# IotaWatt4_1.net
KiCad netlist of a schematic drawn in EAGLE
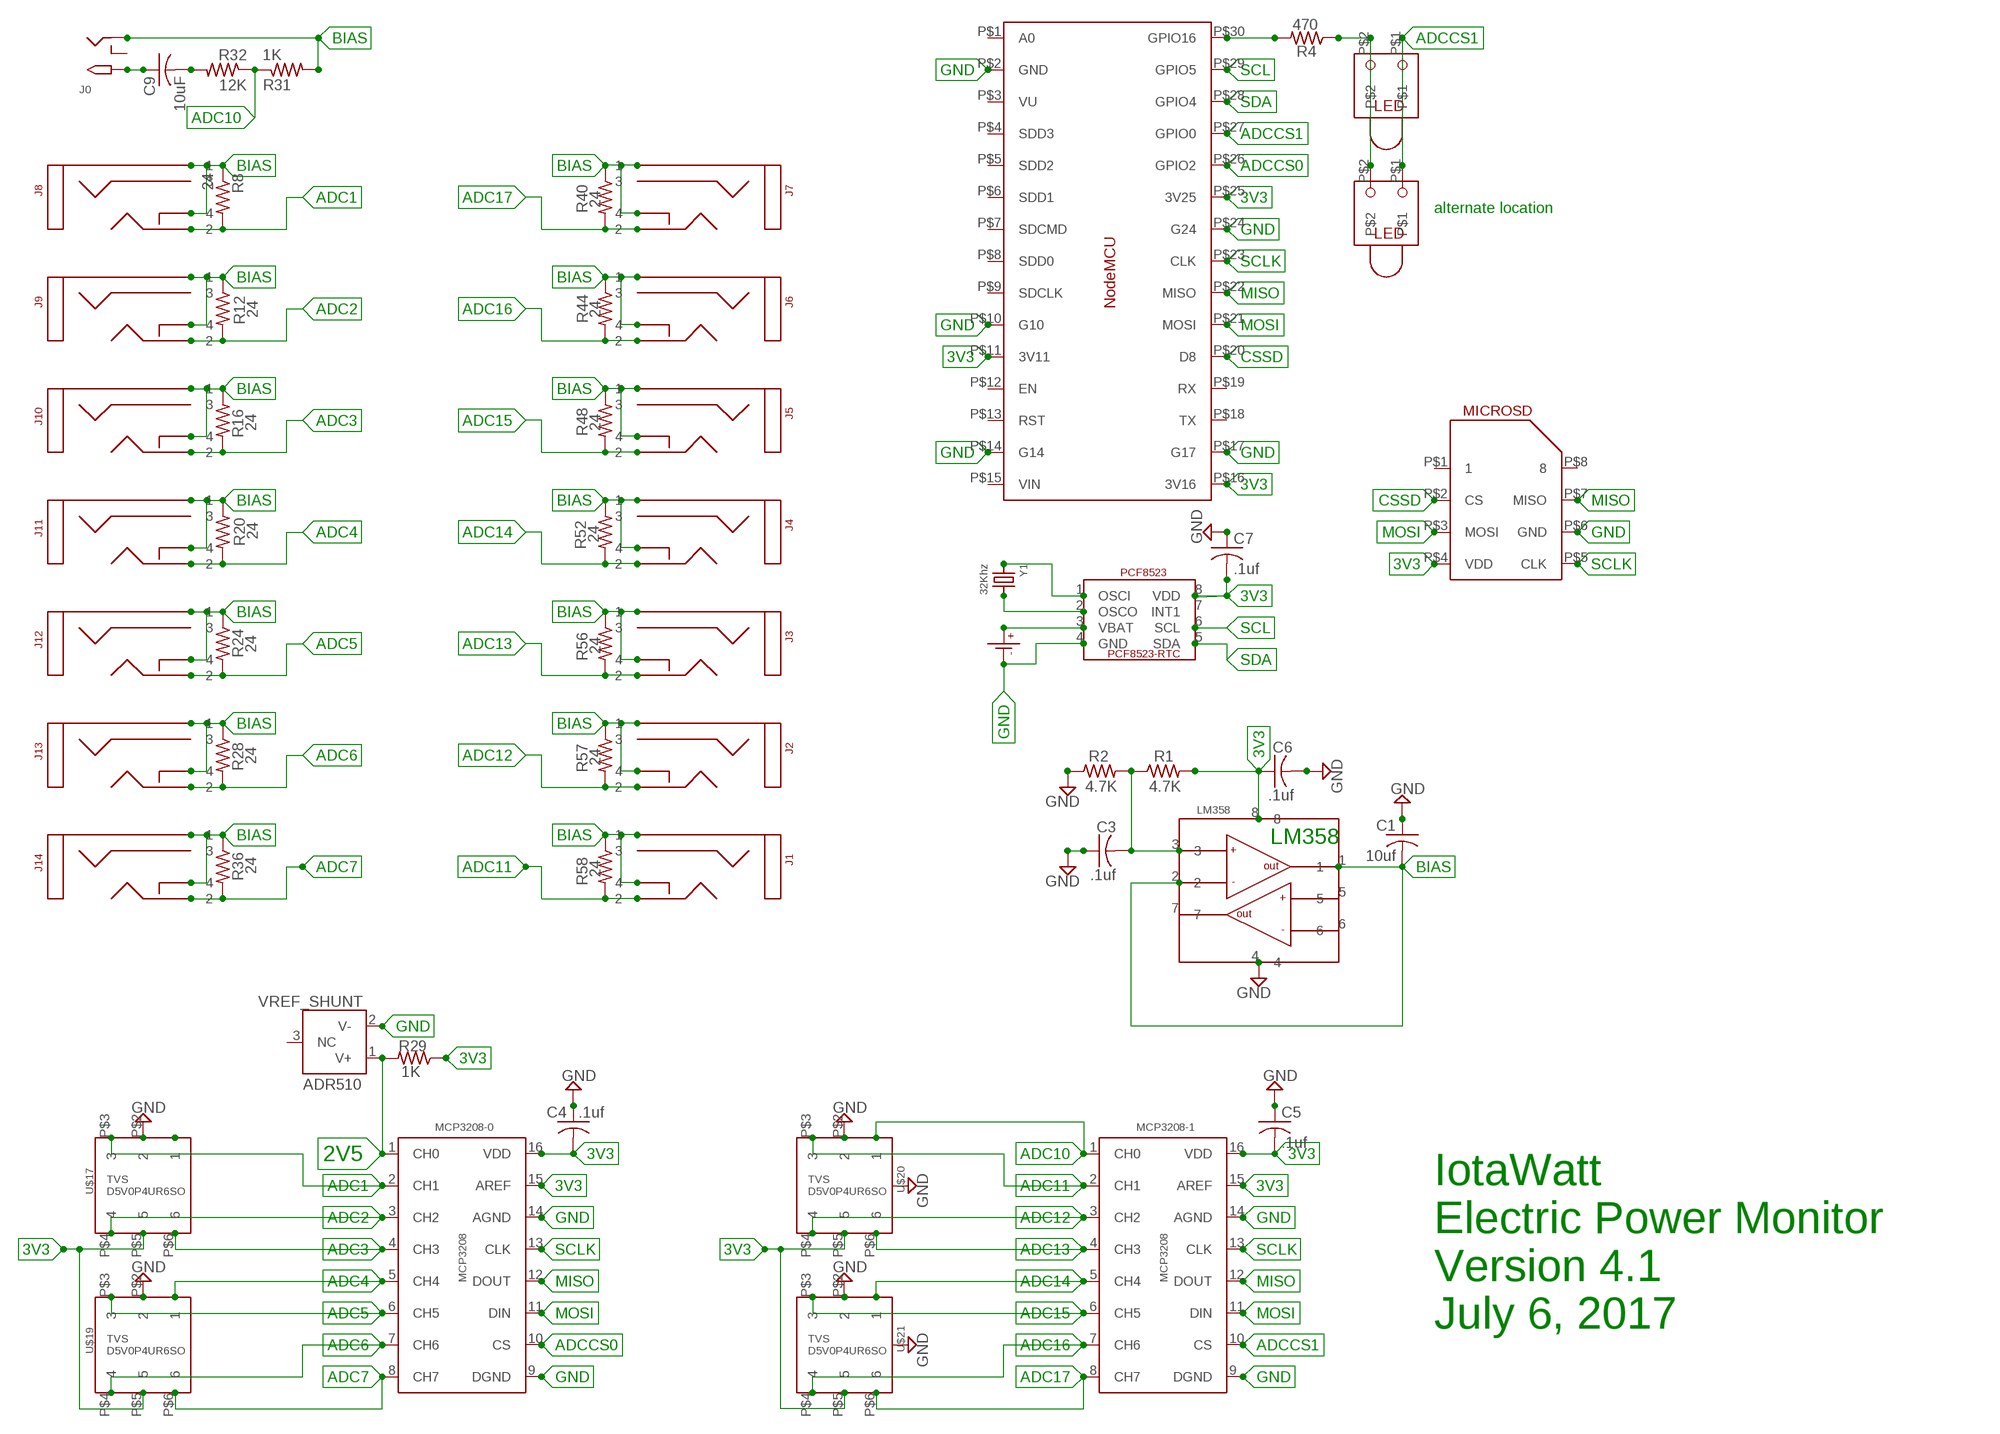
[diagram p0: schematic, sheet 1]

(export (version "E")
  (design (tool "Eeschema 10.0.6"))
  (components
    (comp (ref "ADR510")
      (value "VREF_SHUNT")
      (footprint "eagle-import:SOT23_3")
      (libsource (lib "eagle-import") (part "VREF_SHUNT"))
    )
    (comp (ref "C1")
      (value "10uf")
      (footprint "eagle-import:C0805")
      (libsource (lib "eagle-import") (part "C-USC0805"))
    )
    (comp (ref "C3")
      (value ".1uf")
      (footprint "eagle-import:C0805")
      (libsource (lib "eagle-import") (part "C-USC0805"))
    )
    (comp (ref "C4")
      (value ".1uf")
      (footprint "eagle-import:C0402")
      (libsource (lib "eagle-import") (part "C-USC0402"))
    )
    (comp (ref "C5")
      (value ".1uf")
      (footprint "eagle-import:C0402")
      (libsource (lib "eagle-import") (part "C-USC0402"))
    )
    (comp (ref "C6")
      (value ".1uf")
      (footprint "eagle-import:C0402")
      (libsource (lib "eagle-import") (part "C-USC0402"))
    )
    (comp (ref "C7")
      (value ".1uf")
      (footprint "eagle-import:C0402")
      (libsource (lib "eagle-import") (part "C-USC0402"))
    )
    (comp (ref "C9")
      (value "10uF")
      (footprint "eagle-import:C0805")
      (libsource (lib "eagle-import") (part "C-USC0805"))
    )
    (comp (ref "J0")
      (value "2.1MMJACKSMT")
      (footprint "eagle-import:DCJACK_2MM_SMT")
      (libsource (lib "eagle-import") (part "2.1MMJACKSMT"))
    )
    (comp (ref "J1")
      (value "STEREO_SMD")
      (footprint "eagle-import:STEREO_SMT")
      (libsource (lib "eagle-import") (part "STEREO_SMD"))
    )
    (comp (ref "J2")
      (value "STEREO_SMD")
      (footprint "eagle-import:STEREO_SMT")
      (libsource (lib "eagle-import") (part "STEREO_SMD"))
    )
    (comp (ref "J3")
      (value "STEREO_SMD")
      (footprint "eagle-import:STEREO_SMT")
      (libsource (lib "eagle-import") (part "STEREO_SMD"))
    )
    (comp (ref "J4")
      (value "STEREO_SMD")
      (footprint "eagle-import:STEREO_SMT")
      (libsource (lib "eagle-import") (part "STEREO_SMD"))
    )
    (comp (ref "J5")
      (value "STEREO_SMD")
      (footprint "eagle-import:STEREO_SMT")
      (libsource (lib "eagle-import") (part "STEREO_SMD"))
    )
    (comp (ref "J6")
      (value "STEREO_SMD")
      (footprint "eagle-import:STEREO_SMT")
      (libsource (lib "eagle-import") (part "STEREO_SMD"))
    )
    (comp (ref "J7")
      (value "STEREO_SMD")
      (footprint "eagle-import:STEREO_SMT")
      (libsource (lib "eagle-import") (part "STEREO_SMD"))
    )
    (comp (ref "J8")
      (value "STEREO_SMD")
      (footprint "eagle-import:STEREO_SMT")
      (libsource (lib "eagle-import") (part "STEREO_SMD"))
    )
    (comp (ref "J9")
      (value "STEREO_SMD")
      (footprint "eagle-import:STEREO_SMT")
      (libsource (lib "eagle-import") (part "STEREO_SMD"))
    )
    (comp (ref "J10")
      (value "STEREO_SMD")
      (footprint "eagle-import:STEREO_SMT")
      (libsource (lib "eagle-import") (part "STEREO_SMD"))
    )
    (comp (ref "J11")
      (value "STEREO_SMD")
      (footprint "eagle-import:STEREO_SMT")
      (libsource (lib "eagle-import") (part "STEREO_SMD"))
    )
    (comp (ref "J12")
      (value "STEREO_SMD")
      (footprint "eagle-import:STEREO_SMT")
      (libsource (lib "eagle-import") (part "STEREO_SMD"))
    )
    (comp (ref "J13")
      (value "STEREO_SMD")
      (footprint "eagle-import:STEREO_SMT")
      (libsource (lib "eagle-import") (part "STEREO_SMD"))
    )
    (comp (ref "J14")
      (value "STEREO_SMD")
      (footprint "eagle-import:STEREO_SMT")
      (libsource (lib "eagle-import") (part "STEREO_SMD"))
    )
    (comp (ref "MCP3208-0")
      (value "MCP3208")
      (footprint "eagle-import:SOIC_16")
      (libsource (lib "eagle-import") (part "MCP3208"))
    )
    (comp (ref "MCP3208-1")
      (value "MCP3208")
      (footprint "eagle-import:SOIC_16")
      (libsource (lib "eagle-import") (part "MCP3208"))
    )
    (comp (ref "MICROSD")
      (value "MICROSD_PUSH/PULL")
      (footprint "eagle-import:MICROSD")
      (libsource (lib "eagle-import") (part "MICROSD_PUSH/PULL"))
    )
    (comp (ref "PCF8523")
      (value "PCF8523_RTC")
      (footprint "eagle-import:SOIC_8")
      (libsource (lib "eagle-import") (part "PCF8523_RTC"))
    )
    (comp (ref "R1")
      (value "4.7K")
      (footprint "eagle-import:R0805")
      (libsource (lib "eagle-import") (part "R-US_R0805"))
    )
    (comp (ref "R2")
      (value "4.7K")
      (footprint "eagle-import:R0805")
      (libsource (lib "eagle-import") (part "R-US_R0805"))
    )
    (comp (ref "R4")
      (value "470")
      (footprint "eagle-import:R0805")
      (libsource (lib "eagle-import") (part "R-US_R0805"))
    )
    (comp (ref "R8")
      (value "24")
      (footprint "eagle-import:R0805")
      (libsource (lib "eagle-import") (part "R-US_R0805"))
    )
    (comp (ref "R12")
      (value "24")
      (footprint "eagle-import:R0805")
      (libsource (lib "eagle-import") (part "R-US_R0805"))
    )
    (comp (ref "R16")
      (value "24")
      (footprint "eagle-import:R0805")
      (libsource (lib "eagle-import") (part "R-US_R0805"))
    )
    (comp (ref "R20")
      (value "24")
      (footprint "eagle-import:R0805")
      (libsource (lib "eagle-import") (part "R-US_R0805"))
    )
    (comp (ref "R24")
      (value "24")
      (footprint "eagle-import:R0805")
      (libsource (lib "eagle-import") (part "R-US_R0805"))
    )
    (comp (ref "R28")
      (value "24")
      (footprint "eagle-import:R0805")
      (libsource (lib "eagle-import") (part "R-US_R0805"))
    )
    (comp (ref "R29")
      (value "1K")
      (footprint "eagle-import:R0805")
      (libsource (lib "eagle-import") (part "R-US_R0805"))
    )
    (comp (ref "R31")
      (value "1K")
      (footprint "eagle-import:R0805")
      (libsource (lib "eagle-import") (part "R-US_R0805"))
    )
    (comp (ref "R32")
      (value "12K")
      (footprint "eagle-import:R0805")
      (libsource (lib "eagle-import") (part "R-US_R0805"))
    )
    (comp (ref "R36")
      (value "24")
      (footprint "eagle-import:R0805")
      (libsource (lib "eagle-import") (part "R-US_R0805"))
    )
    (comp (ref "R40")
      (value "24")
      (footprint "eagle-import:R0805")
      (libsource (lib "eagle-import") (part "R-US_R0805"))
    )
    (comp (ref "R44")
      (value "24")
      (footprint "eagle-import:R0805")
      (libsource (lib "eagle-import") (part "R-US_R0805"))
    )
    (comp (ref "R48")
      (value "24")
      (footprint "eagle-import:R0805")
      (libsource (lib "eagle-import") (part "R-US_R0805"))
    )
    (comp (ref "R52")
      (value "24")
      (footprint "eagle-import:R0805")
      (libsource (lib "eagle-import") (part "R-US_R0805"))
    )
    (comp (ref "R56")
      (value "24")
      (footprint "eagle-import:R0805")
      (libsource (lib "eagle-import") (part "R-US_R0805"))
    )
    (comp (ref "R57")
      (value "24")
      (footprint "eagle-import:R0805")
      (libsource (lib "eagle-import") (part "R-US_R0805"))
    )
    (comp (ref "R58")
      (value "24")
      (footprint "eagle-import:R0805")
      (libsource (lib "eagle-import") (part "R-US_R0805"))
    )
    (comp (ref "U$15")
      (value "LED_RT_TRH")
      (footprint "eagle-import:LED_TH_RT")
      (libsource (lib "eagle-import") (part "LED_RT_TRH"))
    )
    (comp (ref "U$16")
      (value "NODEMCU")
      (footprint "eagle-import:NODEMCU")
      (libsource (lib "eagle-import") (part "NODEMCU"))
    )
    (comp (ref "U$17")
      (value "TVS_4CHAN_ARRAY")
      (footprint "eagle-import:SC-74")
      (libsource (lib "eagle-import") (part "TVS_4CHAN_ARRAY"))
    )
    (comp (ref "U$18")
      (value "CR1220SMD")
      (footprint "eagle-import:CR1220SMD")
      (libsource (lib "eagle-import") (part "CR1220SMD"))
    )
    (comp (ref "U$19")
      (value "TVS_4CHAN_ARRAY")
      (footprint "eagle-import:SC-74")
      (libsource (lib "eagle-import") (part "TVS_4CHAN_ARRAY"))
    )
    (comp (ref "U$20")
      (value "TVS_4CHAN_ARRAY")
      (footprint "eagle-import:SC-74")
      (libsource (lib "eagle-import") (part "TVS_4CHAN_ARRAY"))
    )
    (comp (ref "U$21")
      (value "TVS_4CHAN_ARRAY")
      (footprint "eagle-import:SC-74")
      (libsource (lib "eagle-import") (part "TVS_4CHAN_ARRAY"))
    )
    (comp (ref "U$22")
      (value "LM358_DUAL_OP-AMP")
      (footprint "eagle-import:SOIC_8")
      (libsource (lib "eagle-import") (part "LM358_DUAL_OP-AMP"))
    )
    (comp (ref "U$23")
      (value "LED_RT_TRH")
      (footprint "eagle-import:LED_TH_RT")
      (libsource (lib "eagle-import") (part "LED_RT_TRH"))
    )
    (comp (ref "Y1")
      (value "32Khz")
      (footprint "eagle-import:CRYSTAL_8X3.8")
      (libsource (lib "eagle-import") (part "CRYSTAL8X3.8SMT"))
    )
  )
  (nets
    (net (code "1") (name "2V5") (class "Default")
      (node (ref "ADR510") (pin "1") (pinfunction "V+_1") (pintype "bidirectional"))
      (node (ref "MCP3208-0") (pin "1") (pinfunction "CH0_1") (pintype "input"))
      (node (ref "R29") (pin "2") (pinfunction "2_2") (pintype "passive"))
    )
    (net (code "2") (name "3V3") (class "Default")
      (node (ref "C4") (pin "2") (pinfunction "2_2") (pintype "passive"))
      (node (ref "C5") (pin "2") (pinfunction "2_2") (pintype "passive"))
      (node (ref "C6") (pin "1") (pinfunction "1_1") (pintype "passive"))
      (node (ref "C7") (pin "2") (pinfunction "2_2") (pintype "passive"))
      (node (ref "MCP3208-0") (pin "15") (pinfunction "AREF_15") (pintype "input"))
      (node (ref "MCP3208-0") (pin "16") (pinfunction "VDD_16") (pintype "bidirectional"))
      (node (ref "MCP3208-1") (pin "15") (pinfunction "AREF_15") (pintype "input"))
      (node (ref "MCP3208-1") (pin "16") (pinfunction "VDD_16") (pintype "bidirectional"))
      (node (ref "MICROSD") (pin "P$4") (pinfunction "VDD_P$4") (pintype "bidirectional"))
      (node (ref "PCF8523") (pin "8") (pinfunction "VDD_8") (pintype "bidirectional"))
      (node (ref "R1") (pin "2") (pinfunction "2_2") (pintype "passive"))
      (node (ref "R29") (pin "1") (pinfunction "1_1") (pintype "passive"))
      (node (ref "U$16") (pin "P$11") (pinfunction "3V11_P$11") (pintype "bidirectional"))
      (node (ref "U$16") (pin "P$16") (pinfunction "3V16_P$16") (pintype "bidirectional"))
      (node (ref "U$16") (pin "P$25") (pinfunction "3V25_P$25") (pintype "bidirectional"))
      (node (ref "U$17") (pin "P$5") (pinfunction "5_P$5") (pintype "bidirectional"))
      (node (ref "U$19") (pin "P$5") (pinfunction "5_P$5") (pintype "bidirectional"))
      (node (ref "U$20") (pin "P$5") (pinfunction "5_P$5") (pintype "bidirectional"))
      (node (ref "U$21") (pin "P$5") (pinfunction "5_P$5") (pintype "bidirectional"))
      (node (ref "U$22") (pin "8") (pinfunction "8_8") (pintype "bidirectional"))
    )
    (net (code "3") (name "ADC1") (class "Default")
      (node (ref "J8") (pin "P$2") (pinfunction "2_P$2") (pintype "bidirectional"))
      (node (ref "MCP3208-0") (pin "2") (pinfunction "CH1_2") (pintype "input"))
      (node (ref "R8") (pin "2") (pinfunction "2_2") (pintype "passive"))
      (node (ref "U$17") (pin "P$3") (pinfunction "3_P$3") (pintype "bidirectional"))
    )
    (net (code "4") (name "ADC2") (class "Default")
      (node (ref "J9") (pin "P$2") (pinfunction "2_P$2") (pintype "bidirectional"))
      (node (ref "MCP3208-0") (pin "3") (pinfunction "CH2_3") (pintype "input"))
      (node (ref "R12") (pin "2") (pinfunction "2_2") (pintype "passive"))
      (node (ref "U$17") (pin "P$4") (pinfunction "4_P$4") (pintype "bidirectional"))
    )
    (net (code "5") (name "ADC3") (class "Default")
      (node (ref "J10") (pin "P$2") (pinfunction "2_P$2") (pintype "bidirectional"))
      (node (ref "MCP3208-0") (pin "4") (pinfunction "CH3_4") (pintype "input"))
      (node (ref "R16") (pin "2") (pinfunction "2_2") (pintype "passive"))
      (node (ref "U$17") (pin "P$6") (pinfunction "6_P$6") (pintype "bidirectional"))
    )
    (net (code "6") (name "ADC4") (class "Default")
      (node (ref "J11") (pin "P$2") (pinfunction "2_P$2") (pintype "bidirectional"))
      (node (ref "MCP3208-0") (pin "5") (pinfunction "CH4_5") (pintype "bidirectional"))
      (node (ref "R20") (pin "2") (pinfunction "2_2") (pintype "passive"))
      (node (ref "U$19") (pin "P$1") (pinfunction "1_P$1") (pintype "bidirectional"))
    )
    (net (code "7") (name "ADC5") (class "Default")
      (node (ref "J12") (pin "P$2") (pinfunction "2_P$2") (pintype "bidirectional"))
      (node (ref "MCP3208-0") (pin "6") (pinfunction "CH5_6") (pintype "bidirectional"))
      (node (ref "R24") (pin "2") (pinfunction "2_2") (pintype "passive"))
      (node (ref "U$19") (pin "P$3") (pinfunction "3_P$3") (pintype "bidirectional"))
    )
    (net (code "8") (name "ADC6") (class "Default")
      (node (ref "J13") (pin "P$2") (pinfunction "2_P$2") (pintype "bidirectional"))
      (node (ref "MCP3208-0") (pin "7") (pinfunction "CH6_7") (pintype "input"))
      (node (ref "R28") (pin "2") (pinfunction "2_2") (pintype "passive"))
      (node (ref "U$19") (pin "P$4") (pinfunction "4_P$4") (pintype "bidirectional"))
    )
    (net (code "9") (name "ADC7") (class "Default")
      (node (ref "J14") (pin "P$2") (pinfunction "2_P$2") (pintype "bidirectional"))
      (node (ref "MCP3208-0") (pin "8") (pinfunction "CH7_8") (pintype "bidirectional"))
      (node (ref "R36") (pin "2") (pinfunction "2_2") (pintype "passive"))
      (node (ref "U$19") (pin "P$6") (pinfunction "6_P$6") (pintype "bidirectional"))
    )
    (net (code "10") (name "ADC10") (class "Default")
      (node (ref "MCP3208-1") (pin "1") (pinfunction "CH0_1") (pintype "input"))
      (node (ref "R31") (pin "1") (pinfunction "1_1") (pintype "passive"))
      (node (ref "R32") (pin "1") (pinfunction "1_1") (pintype "passive"))
      (node (ref "U$20") (pin "P$1") (pinfunction "1_P$1") (pintype "bidirectional"))
    )
    (net (code "11") (name "ADC11") (class "Default")
      (node (ref "J1") (pin "P$2") (pinfunction "2_P$2") (pintype "bidirectional"))
      (node (ref "MCP3208-1") (pin "2") (pinfunction "CH1_2") (pintype "input"))
      (node (ref "R58") (pin "2") (pinfunction "2_2") (pintype "passive"))
      (node (ref "U$20") (pin "P$3") (pinfunction "3_P$3") (pintype "bidirectional"))
    )
    (net (code "12") (name "ADC12") (class "Default")
      (node (ref "J2") (pin "P$2") (pinfunction "2_P$2") (pintype "bidirectional"))
      (node (ref "MCP3208-1") (pin "3") (pinfunction "CH2_3") (pintype "input"))
      (node (ref "R57") (pin "2") (pinfunction "2_2") (pintype "passive"))
      (node (ref "U$20") (pin "P$4") (pinfunction "4_P$4") (pintype "bidirectional"))
    )
    (net (code "13") (name "ADC13") (class "Default")
      (node (ref "J3") (pin "P$2") (pinfunction "2_P$2") (pintype "bidirectional"))
      (node (ref "MCP3208-1") (pin "4") (pinfunction "CH3_4") (pintype "input"))
      (node (ref "R56") (pin "2") (pinfunction "2_2") (pintype "passive"))
      (node (ref "U$20") (pin "P$6") (pinfunction "6_P$6") (pintype "bidirectional"))
    )
    (net (code "14") (name "ADC14") (class "Default")
      (node (ref "J4") (pin "P$2") (pinfunction "2_P$2") (pintype "bidirectional"))
      (node (ref "MCP3208-1") (pin "5") (pinfunction "CH4_5") (pintype "bidirectional"))
      (node (ref "R52") (pin "2") (pinfunction "2_2") (pintype "passive"))
      (node (ref "U$21") (pin "P$1") (pinfunction "1_P$1") (pintype "bidirectional"))
    )
    (net (code "15") (name "ADC15") (class "Default")
      (node (ref "J5") (pin "P$2") (pinfunction "2_P$2") (pintype "bidirectional"))
      (node (ref "MCP3208-1") (pin "6") (pinfunction "CH5_6") (pintype "bidirectional"))
      (node (ref "R48") (pin "2") (pinfunction "2_2") (pintype "passive"))
      (node (ref "U$21") (pin "P$3") (pinfunction "3_P$3") (pintype "bidirectional"))
    )
    (net (code "16") (name "ADC16") (class "Default")
      (node (ref "J6") (pin "P$2") (pinfunction "2_P$2") (pintype "bidirectional"))
      (node (ref "MCP3208-1") (pin "7") (pinfunction "CH6_7") (pintype "input"))
      (node (ref "R44") (pin "2") (pinfunction "2_2") (pintype "passive"))
      (node (ref "U$21") (pin "P$4") (pinfunction "4_P$4") (pintype "bidirectional"))
    )
    (net (code "17") (name "ADC17") (class "Default")
      (node (ref "J7") (pin "P$2") (pinfunction "2_P$2") (pintype "bidirectional"))
      (node (ref "MCP3208-1") (pin "8") (pinfunction "CH7_8") (pintype "bidirectional"))
      (node (ref "R40") (pin "2") (pinfunction "2_2") (pintype "passive"))
      (node (ref "U$21") (pin "P$6") (pinfunction "6_P$6") (pintype "bidirectional"))
    )
    (net (code "18") (name "ADCCS0") (class "Default")
      (node (ref "MCP3208-0") (pin "10") (pinfunction "CS_10") (pintype "input"))
      (node (ref "U$16") (pin "P$26") (pinfunction "GPIO2_P$26") (pintype "bidirectional"))
    )
    (net (code "19") (name "ADCCS1") (class "Default")
      (node (ref "MCP3208-1") (pin "10") (pinfunction "CS_10") (pintype "input"))
      (node (ref "U$15") (pin "P$1") (pinfunction "P$1_P$1") (pintype "bidirectional"))
      (node (ref "U$16") (pin "P$27") (pinfunction "GPIO0_P$27") (pintype "bidirectional"))
      (node (ref "U$23") (pin "P$1") (pinfunction "P$1_P$1") (pintype "bidirectional"))
    )
    (net (code "20") (name "BIAS") (class "Default")
      (node (ref "C1") (pin "2") (pinfunction "2_2") (pintype "passive"))
      (node (ref "J0") (pin "GND") (pinfunction "RING_GND") (pintype "bidirectional"))
      (node (ref "J1") (pin "P$1") (pinfunction "1_P$1") (pintype "bidirectional"))
      (node (ref "J1") (pin "P$4") (pinfunction "4_P$4") (pintype "bidirectional"))
      (node (ref "J10") (pin "P$1") (pinfunction "1_P$1") (pintype "bidirectional"))
      (node (ref "J10") (pin "P$4") (pinfunction "4_P$4") (pintype "bidirectional"))
      (node (ref "J11") (pin "P$1") (pinfunction "1_P$1") (pintype "bidirectional"))
      (node (ref "J11") (pin "P$4") (pinfunction "4_P$4") (pintype "bidirectional"))
      (node (ref "J12") (pin "P$1") (pinfunction "1_P$1") (pintype "bidirectional"))
      (node (ref "J12") (pin "P$4") (pinfunction "4_P$4") (pintype "bidirectional"))
      (node (ref "J13") (pin "P$1") (pinfunction "1_P$1") (pintype "bidirectional"))
      (node (ref "J13") (pin "P$4") (pinfunction "4_P$4") (pintype "bidirectional"))
      (node (ref "J14") (pin "P$1") (pinfunction "1_P$1") (pintype "bidirectional"))
      (node (ref "J14") (pin "P$4") (pinfunction "4_P$4") (pintype "bidirectional"))
      (node (ref "J2") (pin "P$1") (pinfunction "1_P$1") (pintype "bidirectional"))
      (node (ref "J2") (pin "P$4") (pinfunction "4_P$4") (pintype "bidirectional"))
      (node (ref "J3") (pin "P$1") (pinfunction "1_P$1") (pintype "bidirectional"))
      (node (ref "J3") (pin "P$4") (pinfunction "4_P$4") (pintype "bidirectional"))
      (node (ref "J4") (pin "P$1") (pinfunction "1_P$1") (pintype "bidirectional"))
      (node (ref "J4") (pin "P$4") (pinfunction "4_P$4") (pintype "bidirectional"))
      (node (ref "J5") (pin "P$1") (pinfunction "1_P$1") (pintype "bidirectional"))
      (node (ref "J5") (pin "P$4") (pinfunction "4_P$4") (pintype "bidirectional"))
      (node (ref "J6") (pin "P$1") (pinfunction "1_P$1") (pintype "bidirectional"))
      (node (ref "J6") (pin "P$4") (pinfunction "4_P$4") (pintype "bidirectional"))
      (node (ref "J7") (pin "P$1") (pinfunction "1_P$1") (pintype "bidirectional"))
      (node (ref "J7") (pin "P$4") (pinfunction "4_P$4") (pintype "bidirectional"))
      (node (ref "J8") (pin "P$1") (pinfunction "1_P$1") (pintype "bidirectional"))
      (node (ref "J8") (pin "P$4") (pinfunction "4_P$4") (pintype "bidirectional"))
      (node (ref "J9") (pin "P$1") (pinfunction "1_P$1") (pintype "bidirectional"))
      (node (ref "J9") (pin "P$4") (pinfunction "4_P$4") (pintype "bidirectional"))
      (node (ref "R12") (pin "1") (pinfunction "1_1") (pintype "passive"))
      (node (ref "R16") (pin "1") (pinfunction "1_1") (pintype "passive"))
      (node (ref "R20") (pin "1") (pinfunction "1_1") (pintype "passive"))
      (node (ref "R24") (pin "1") (pinfunction "1_1") (pintype "passive"))
      (node (ref "R28") (pin "1") (pinfunction "1_1") (pintype "passive"))
      (node (ref "R31") (pin "2") (pinfunction "2_2") (pintype "passive"))
      (node (ref "R36") (pin "1") (pinfunction "1_1") (pintype "passive"))
      (node (ref "R40") (pin "1") (pinfunction "1_1") (pintype "passive"))
      (node (ref "R44") (pin "1") (pinfunction "1_1") (pintype "passive"))
      (node (ref "R48") (pin "1") (pinfunction "1_1") (pintype "passive"))
      (node (ref "R52") (pin "1") (pinfunction "1_1") (pintype "passive"))
      (node (ref "R56") (pin "1") (pinfunction "1_1") (pintype "passive"))
      (node (ref "R57") (pin "1") (pinfunction "1_1") (pintype "passive"))
      (node (ref "R58") (pin "1") (pinfunction "1_1") (pintype "passive"))
      (node (ref "R8") (pin "1") (pinfunction "1_1") (pintype "passive"))
      (node (ref "U$22") (pin "1") (pinfunction "1_1") (pintype "bidirectional"))
      (node (ref "U$22") (pin "2") (pinfunction "2_2") (pintype "bidirectional"))
    )
    (net (code "21") (name "CSSD") (class "Default")
      (node (ref "MICROSD") (pin "P$2") (pinfunction "CS_P$2") (pintype "bidirectional"))
      (node (ref "U$16") (pin "P$20") (pinfunction "D8_P$20") (pintype "bidirectional"))
    )
    (net (code "22") (name "GND") (class "Default")
      (node (ref "ADR510") (pin "2") (pinfunction "V-_2") (pintype "bidirectional"))
      (node (ref "C1") (pin "1") (pinfunction "1_1") (pintype "passive"))
      (node (ref "C3") (pin "1") (pinfunction "1_1") (pintype "passive"))
      (node (ref "C4") (pin "1") (pinfunction "1_1") (pintype "passive"))
      (node (ref "C5") (pin "1") (pinfunction "1_1") (pintype "passive"))
      (node (ref "C6") (pin "2") (pinfunction "2_2") (pintype "passive"))
      (node (ref "C7") (pin "1") (pinfunction "1_1") (pintype "passive"))
      (node (ref "MCP3208-0") (pin "14") (pinfunction "AGND_14") (pintype "input"))
      (node (ref "MCP3208-0") (pin "9") (pinfunction "DGND_9") (pintype "bidirectional"))
      (node (ref "MCP3208-1") (pin "14") (pinfunction "AGND_14") (pintype "input"))
      (node (ref "MCP3208-1") (pin "9") (pinfunction "DGND_9") (pintype "bidirectional"))
      (node (ref "MICROSD") (pin "P$6") (pinfunction "GND_P$6") (pintype "bidirectional"))
      (node (ref "PCF8523") (pin "4") (pinfunction "GND_4") (pintype "bidirectional"))
      (node (ref "R2") (pin "1") (pinfunction "1_1") (pintype "passive"))
      (node (ref "U$16") (pin "P$10") (pinfunction "G10_P$10") (pintype "bidirectional"))
      (node (ref "U$16") (pin "P$14") (pinfunction "G14_P$14") (pintype "bidirectional"))
      (node (ref "U$16") (pin "P$17") (pinfunction "G17_P$17") (pintype "bidirectional"))
      (node (ref "U$16") (pin "P$2") (pinfunction "GND_P$2") (pintype "bidirectional"))
      (node (ref "U$16") (pin "P$24") (pinfunction "G24_P$24") (pintype "bidirectional"))
      (node (ref "U$17") (pin "P$2") (pinfunction "2_P$2") (pintype "bidirectional"))
      (node (ref "U$18") (pin "P-") (pinfunction "P$-_P-") (pintype "bidirectional"))
      (node (ref "U$19") (pin "P$2") (pinfunction "2_P$2") (pintype "bidirectional"))
      (node (ref "U$20") (pin "P$2") (pinfunction "2_P$2") (pintype "bidirectional"))
      (node (ref "U$21") (pin "P$2") (pinfunction "2_P$2") (pintype "bidirectional"))
      (node (ref "U$22") (pin "4") (pinfunction "4_4") (pintype "bidirectional"))
    )
    (net (code "23") (name "MISO") (class "Default")
      (node (ref "MCP3208-0") (pin "12") (pinfunction "DOUT_12") (pintype "bidirectional"))
      (node (ref "MCP3208-1") (pin "12") (pinfunction "DOUT_12") (pintype "bidirectional"))
      (node (ref "MICROSD") (pin "P$7") (pinfunction "MISO_P$7") (pintype "bidirectional"))
      (node (ref "U$16") (pin "P$22") (pinfunction "MISO_P$22") (pintype "bidirectional"))
    )
    (net (code "24") (name "MOSI") (class "Default")
      (node (ref "MCP3208-0") (pin "11") (pinfunction "DIN_11") (pintype "input"))
      (node (ref "MCP3208-1") (pin "11") (pinfunction "DIN_11") (pintype "input"))
      (node (ref "MICROSD") (pin "P$3") (pinfunction "MOSI_P$3") (pintype "bidirectional"))
      (node (ref "U$16") (pin "P$21") (pinfunction "MOSI_P$21") (pintype "bidirectional"))
    )
    (net (code "25") (name "Net-(C3-Pad2)") (class "Default")
      (node (ref "C3") (pin "2") (pinfunction "2_2") (pintype "passive"))
      (node (ref "R1") (pin "1") (pinfunction "1_1") (pintype "passive"))
      (node (ref "R2") (pin "2") (pinfunction "2_2") (pintype "passive"))
      (node (ref "U$22") (pin "3") (pinfunction "3_3") (pintype "bidirectional"))
    )
    (net (code "26") (name "Net-(C9-Pad2)") (class "Default")
      (node (ref "C9") (pin "2") (pinfunction "2_2") (pintype "passive"))
      (node (ref "R32") (pin "2") (pinfunction "2_2") (pintype "passive"))
    )
    (net (code "27") (name "Net-(J0-TIP)") (class "Default")
      (node (ref "C9") (pin "1") (pinfunction "1_1") (pintype "passive"))
      (node (ref "J0") (pin "PWR2") (pinfunction "TIP_PWR2") (pintype "bidirectional"))
    )
    (net (code "28") (name "Net-(PCF8523-OSCI)") (class "Default")
      (node (ref "PCF8523") (pin "1") (pinfunction "OSCI_1") (pintype "bidirectional"))
      (node (ref "Y1") (pin "P$1") (pinfunction "1_P$1") (pintype "passive"))
    )
    (net (code "29") (name "Net-(PCF8523-OSCO)") (class "Default")
      (node (ref "PCF8523") (pin "2") (pinfunction "OSCO_2") (pintype "bidirectional"))
      (node (ref "Y1") (pin "P$4") (pinfunction "2_P$4") (pintype "passive"))
    )
    (net (code "30") (name "Net-(PCF8523-VBAT)") (class "Default")
      (node (ref "PCF8523") (pin "3") (pinfunction "VBAT_3") (pintype "bidirectional"))
      (node (ref "U$18") (pin "P+") (pinfunction "P$+_P+") (pintype "bidirectional"))
    )
    (net (code "31") (name "Net-(R4-Pad1)") (class "Default")
      (node (ref "R4") (pin "1") (pinfunction "1_1") (pintype "passive"))
      (node (ref "U$15") (pin "P$2") (pinfunction "P$2_P$2") (pintype "bidirectional"))
      (node (ref "U$23") (pin "P$2") (pinfunction "P$2_P$2") (pintype "bidirectional"))
    )
    (net (code "32") (name "Net-(U$16-GPIO16)") (class "Default")
      (node (ref "R4") (pin "2") (pinfunction "2_2") (pintype "passive"))
      (node (ref "U$16") (pin "P$30") (pinfunction "GPIO16_P$30") (pintype "bidirectional"))
    )
    (net (code "33") (name "SCL") (class "Default")
      (node (ref "PCF8523") (pin "6") (pinfunction "SCL_6") (pintype "bidirectional"))
      (node (ref "U$16") (pin "P$29") (pinfunction "GPIO5_P$29") (pintype "bidirectional"))
    )
    (net (code "34") (name "SCLK") (class "Default")
      (node (ref "MCP3208-0") (pin "13") (pinfunction "CLK_13") (pintype "input"))
      (node (ref "MCP3208-1") (pin "13") (pinfunction "CLK_13") (pintype "input"))
      (node (ref "MICROSD") (pin "P$5") (pinfunction "CLK_P$5") (pintype "bidirectional"))
      (node (ref "U$16") (pin "P$23") (pinfunction "CLK_P$23") (pintype "bidirectional"))
    )
    (net (code "35") (name "SDA") (class "Default")
      (node (ref "PCF8523") (pin "5") (pinfunction "SDA_5") (pintype "bidirectional"))
      (node (ref "U$16") (pin "P$28") (pinfunction "GPIO4_P$28") (pintype "bidirectional"))
    )
    (net (code "36") (name "unconnected-(ADR510-NC-Pad3)") (class "Default")
      (node (ref "ADR510") (pin "3") (pinfunction "NC_3") (pintype "bidirectional"))
    )
    (net (code "37") (name "unconnected-(J0-RING_SW-PadGNDBREAK)") (class "Default")
      (node (ref "J0") (pin "GNDBREAK") (pinfunction "RING_SW_GNDBREAK") (pintype "bidirectional"))
    )
    (net (code "38") (name "unconnected-(J1-3-PadP$3)") (class "Default")
      (node (ref "J1") (pin "P$3") (pinfunction "3_P$3") (pintype "bidirectional"))
    )
    (net (code "39") (name "unconnected-(J2-3-PadP$3)") (class "Default")
      (node (ref "J2") (pin "P$3") (pinfunction "3_P$3") (pintype "bidirectional"))
    )
    (net (code "40") (name "unconnected-(J3-3-PadP$3)") (class "Default")
      (node (ref "J3") (pin "P$3") (pinfunction "3_P$3") (pintype "bidirectional"))
    )
    (net (code "41") (name "unconnected-(J4-3-PadP$3)") (class "Default")
      (node (ref "J4") (pin "P$3") (pinfunction "3_P$3") (pintype "bidirectional"))
    )
    (net (code "42") (name "unconnected-(J5-3-PadP$3)") (class "Default")
      (node (ref "J5") (pin "P$3") (pinfunction "3_P$3") (pintype "bidirectional"))
    )
    (net (code "43") (name "unconnected-(J6-3-PadP$3)") (class "Default")
      (node (ref "J6") (pin "P$3") (pinfunction "3_P$3") (pintype "bidirectional"))
    )
    (net (code "44") (name "unconnected-(J7-3-PadP$3)") (class "Default")
      (node (ref "J7") (pin "P$3") (pinfunction "3_P$3") (pintype "bidirectional"))
    )
    (net (code "45") (name "unconnected-(J8-3-PadP$3)") (class "Default")
      (node (ref "J8") (pin "P$3") (pinfunction "3_P$3") (pintype "bidirectional"))
    )
    (net (code "46") (name "unconnected-(J9-3-PadP$3)") (class "Default")
      (node (ref "J9") (pin "P$3") (pinfunction "3_P$3") (pintype "bidirectional"))
    )
    (net (code "47") (name "unconnected-(J10-3-PadP$3)") (class "Default")
      (node (ref "J10") (pin "P$3") (pinfunction "3_P$3") (pintype "bidirectional"))
    )
    (net (code "48") (name "unconnected-(J11-3-PadP$3)") (class "Default")
      (node (ref "J11") (pin "P$3") (pinfunction "3_P$3") (pintype "bidirectional"))
    )
    (net (code "49") (name "unconnected-(J12-3-PadP$3)") (class "Default")
      (node (ref "J12") (pin "P$3") (pinfunction "3_P$3") (pintype "bidirectional"))
    )
    (net (code "50") (name "unconnected-(J13-3-PadP$3)") (class "Default")
      (node (ref "J13") (pin "P$3") (pinfunction "3_P$3") (pintype "bidirectional"))
    )
    (net (code "51") (name "unconnected-(J14-3-PadP$3)") (class "Default")
      (node (ref "J14") (pin "P$3") (pinfunction "3_P$3") (pintype "bidirectional"))
    )
    (net (code "52") (name "unconnected-(MICROSD-1-PadP$1)") (class "Default")
      (node (ref "MICROSD") (pin "P$1") (pinfunction "1_P$1") (pintype "bidirectional"))
    )
    (net (code "53") (name "unconnected-(MICROSD-8-PadP$8)") (class "Default")
      (node (ref "MICROSD") (pin "P$8") (pinfunction "8_P$8") (pintype "bidirectional"))
    )
    (net (code "54") (name "unconnected-(PCF8523-INT1-Pad7)") (class "Default")
      (node (ref "PCF8523") (pin "7") (pinfunction "INT1_7") (pintype "bidirectional"))
    )
    (net (code "55") (name "unconnected-(U$16-A0-PadP$1)") (class "Default")
      (node (ref "U$16") (pin "P$1") (pinfunction "A0_P$1") (pintype "bidirectional"))
    )
    (net (code "56") (name "unconnected-(U$16-EN-PadP$12)") (class "Default")
      (node (ref "U$16") (pin "P$12") (pinfunction "EN_P$12") (pintype "bidirectional"))
    )
    (net (code "57") (name "unconnected-(U$16-RST-PadP$13)") (class "Default")
      (node (ref "U$16") (pin "P$13") (pinfunction "RST_P$13") (pintype "bidirectional"))
    )
    (net (code "58") (name "unconnected-(U$16-RX-PadP$19)") (class "Default")
      (node (ref "U$16") (pin "P$19") (pinfunction "RX_P$19") (pintype "bidirectional"))
    )
    (net (code "59") (name "unconnected-(U$16-SDCLK-PadP$9)") (class "Default")
      (node (ref "U$16") (pin "P$9") (pinfunction "SDCLK_P$9") (pintype "bidirectional"))
    )
    (net (code "60") (name "unconnected-(U$16-SDCMD-PadP$7)") (class "Default")
      (node (ref "U$16") (pin "P$7") (pinfunction "SDCMD_P$7") (pintype "bidirectional"))
    )
    (net (code "61") (name "unconnected-(U$16-SDD0-PadP$8)") (class "Default")
      (node (ref "U$16") (pin "P$8") (pinfunction "SDD0_P$8") (pintype "bidirectional"))
    )
    (net (code "62") (name "unconnected-(U$16-SDD1-PadP$6)") (class "Default")
      (node (ref "U$16") (pin "P$6") (pinfunction "SDD1_P$6") (pintype "bidirectional"))
    )
    (net (code "63") (name "unconnected-(U$16-SDD2-PadP$5)") (class "Default")
      (node (ref "U$16") (pin "P$5") (pinfunction "SDD2_P$5") (pintype "bidirectional"))
    )
    (net (code "64") (name "unconnected-(U$16-SDD3-PadP$4)") (class "Default")
      (node (ref "U$16") (pin "P$4") (pinfunction "SDD3_P$4") (pintype "bidirectional"))
    )
    (net (code "65") (name "unconnected-(U$16-TX-PadP$18)") (class "Default")
      (node (ref "U$16") (pin "P$18") (pinfunction "TX_P$18") (pintype "bidirectional"))
    )
    (net (code "66") (name "unconnected-(U$16-VIN-PadP$15)") (class "Default")
      (node (ref "U$16") (pin "P$15") (pinfunction "VIN_P$15") (pintype "bidirectional"))
    )
    (net (code "67") (name "unconnected-(U$16-VU-PadP$3)") (class "Default")
      (node (ref "U$16") (pin "P$3") (pinfunction "VU_P$3") (pintype "bidirectional"))
    )
    (net (code "68") (name "unconnected-(U$17-1-PadP$1)") (class "Default")
      (node (ref "U$17") (pin "P$1") (pinfunction "1_P$1") (pintype "bidirectional"))
    )
    (net (code "69") (name "unconnected-(U$22-Pad5)") (class "Default")
      (node (ref "U$22") (pin "5") (pinfunction "5_5") (pintype "bidirectional"))
    )
    (net (code "70") (name "unconnected-(U$22-Pad6)") (class "Default")
      (node (ref "U$22") (pin "6") (pinfunction "6_6") (pintype "bidirectional"))
    )
    (net (code "71") (name "unconnected-(U$22-Pad7)") (class "Default")
      (node (ref "U$22") (pin "7") (pinfunction "7_7") (pintype "bidirectional"))
    )
  )
)
